# 9046.net
KiCad netlist of a schematic drawn in Altium Designer
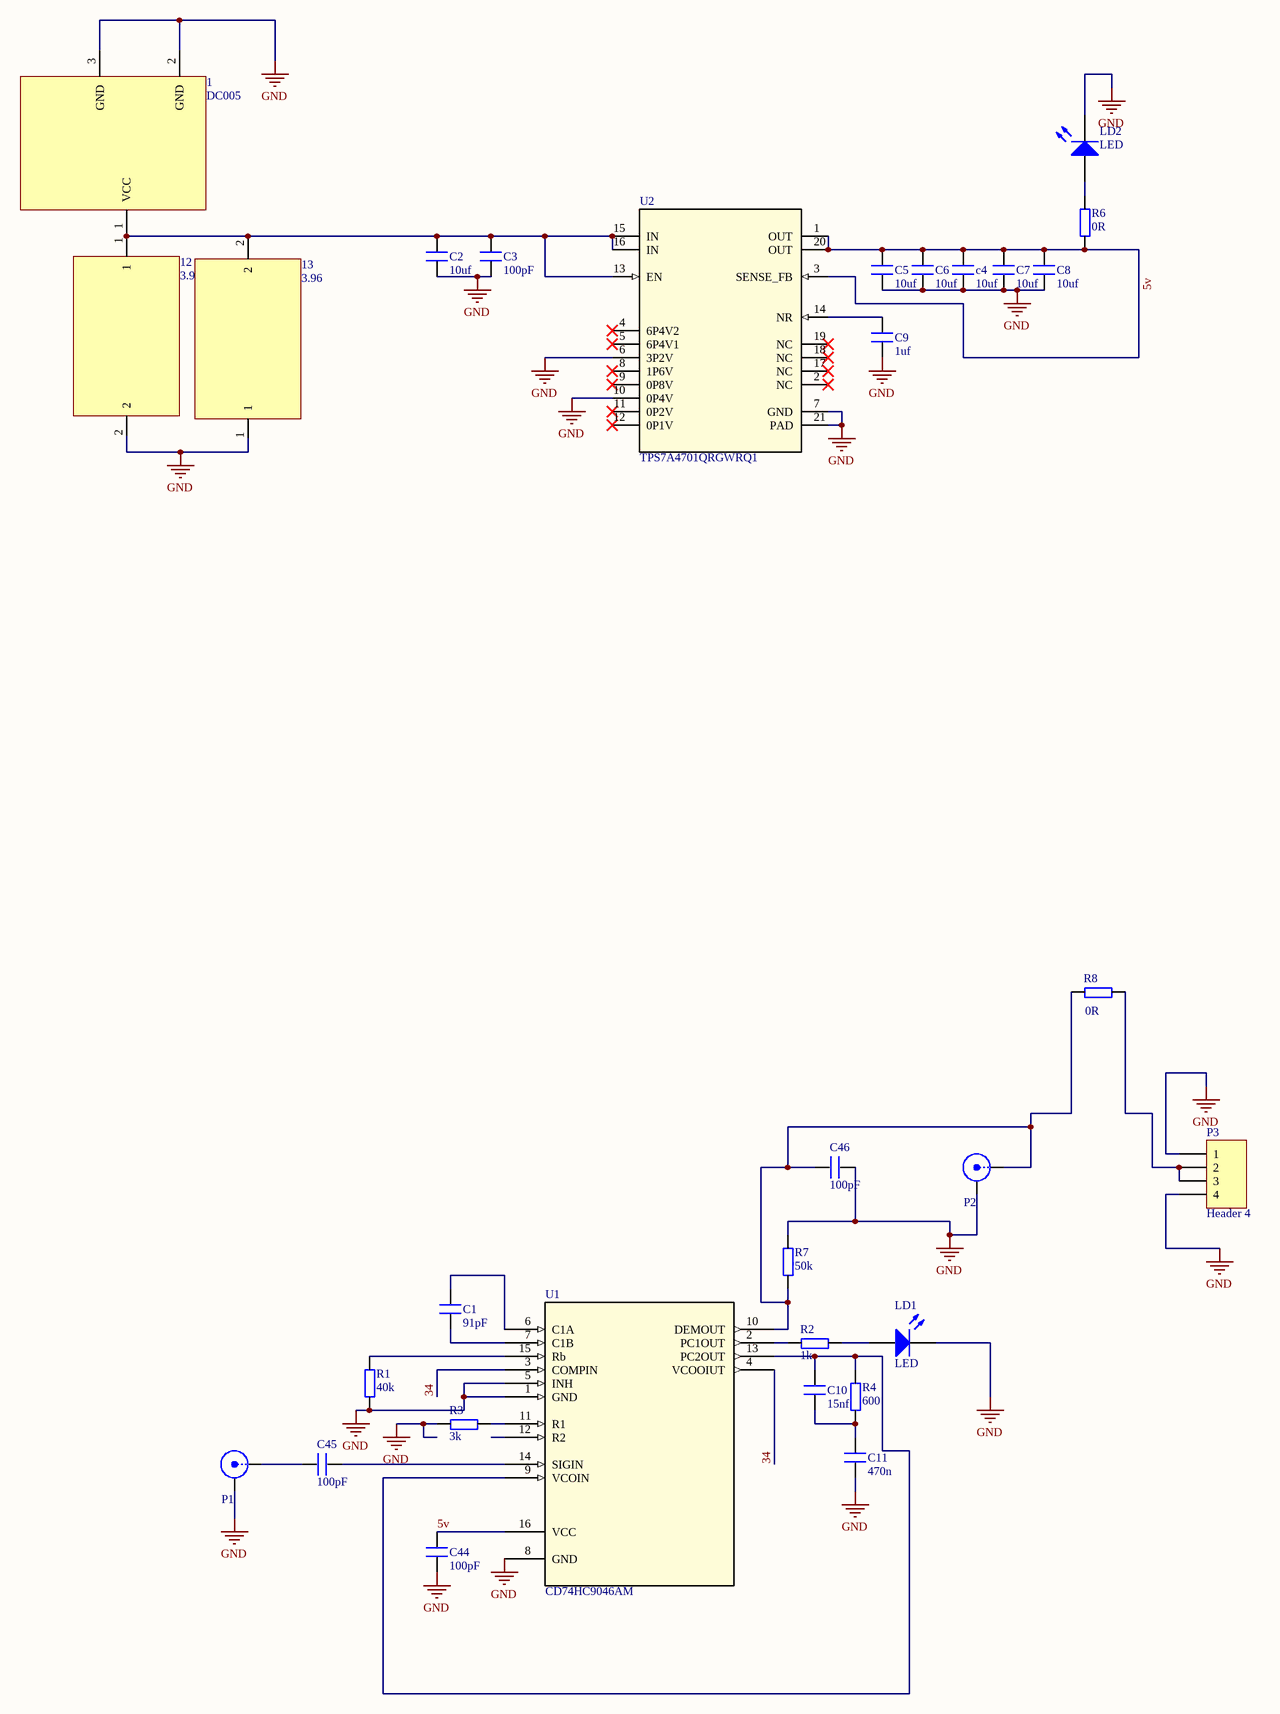
[diagram p0: 9046.SchDoc]

(export (version "E")
  (design (tool "Eeschema 10.0.6"))
  (components
    (comp (ref "1") (value "DC005") (footprint "DC10B") (libsource (lib "MYLIB") (part "DC005")))
    (comp (ref "12") (value "3.96") (footprint "3.96") (libsource (lib "MYLIB") (part "3.96")))
    (comp (ref "13") (value "3.96") (footprint "3.96") (libsource (lib "") (part "3.96_1")))
    (comp (ref "C1")
      (value "91pF")
      (footprint "0603C")
      (description "Capacitor")
      (libsource (lib "MYLIB") (part "C"))
    )
    (comp (ref "C2")
      (value "10uf")
      (footprint "0603C")
      (description "Capacitor")
      (libsource (lib "MYLIB") (part "C"))
    )
    (comp (ref "C3")
      (value "100pF")
      (footprint "0603C")
      (description "Capacitor")
      (libsource (lib "MYLIB") (part "C"))
    )
    (comp (ref "c4")
      (value "10uf")
      (footprint "0603C")
      (description "Capacitor")
      (libsource (lib "MYLIB") (part "C"))
    )
    (comp (ref "C5")
      (value "10uf")
      (footprint "0603C")
      (description "Capacitor")
      (libsource (lib "MYLIB") (part "C"))
    )
    (comp (ref "C6")
      (value "10uf")
      (footprint "0603C")
      (description "Capacitor")
      (libsource (lib "MYLIB") (part "C"))
    )
    (comp (ref "C7")
      (value "10uf")
      (footprint "0603C")
      (description "Capacitor")
      (libsource (lib "MYLIB") (part "C"))
    )
    (comp (ref "C8")
      (value "10uf")
      (footprint "0603C")
      (description "Capacitor")
      (libsource (lib "MYLIB") (part "C"))
    )
    (comp (ref "C9")
      (value "1uf")
      (footprint "0603C")
      (description "Capacitor")
      (libsource (lib "MYLIB") (part "C"))
    )
    (comp (ref "C10")
      (value "15nf")
      (footprint "0603C")
      (description "Capacitor")
      (libsource (lib "MYLIB") (part "C"))
    )
    (comp (ref "C11")
      (value "470n")
      (footprint "0603C")
      (description "Capacitor")
      (libsource (lib "MYLIB") (part "C"))
    )
    (comp (ref "C44")
      (value "100pF")
      (footprint "0603C")
      (description "Capacitor")
      (libsource (lib "MYLIB") (part "C"))
    )
    (comp (ref "C45")
      (value "100pF")
      (footprint "0603C")
      (description "Capacitor")
      (libsource (lib "MYLIB") (part "C"))
    )
    (comp (ref "C46")
      (value "100pF")
      (footprint "0603C")
      (description "Capacitor")
      (libsource (lib "MYLIB") (part "C"))
    )
    (comp (ref "LD1")
      (value "LED")
      (footprint "SMDLED")
      (description "Typical RED, GREEN, YELLOW, AMBER GaAs LED")
      (fields (field (name "PUBLISHER") "Altium Limited"))
      (libsource (lib "MYLIB") (part "LED"))
    )
    (comp (ref "LD2")
      (value "LED")
      (footprint "SMDLED")
      (description "Typical RED, GREEN, YELLOW, AMBER GaAs LED")
      (fields (field (name "PUBLISHER") "Altium Limited"))
      (libsource (lib "MYLIB") (part "LED"))
    )
    (comp (ref "P1")
      (value "SMA")
      (footprint "SMA")
      (description "SMA Connector")
      (libsource (lib "MYLIB") (part "SMA"))
    )
    (comp (ref "P2")
      (value "SMA")
      (footprint "SMA")
      (description "SMA Connector")
      (libsource (lib "MYLIB") (part "SMA"))
    )
    (comp (ref "P3")
      (value "Header 4")
      (footprint "HDR1X4")
      (description "Header, 4-Pin")
      (fields (field (name "PUBLISHER") "Altium Limited"))
      (libsource (lib "MYLIB") (part "Header 4"))
    )
    (comp (ref "R1")
      (value "40k")
      (footprint "0603R")
      (description "Resistor")
      (libsource (lib "MYLIB") (part "Resistor"))
    )
    (comp (ref "R2")
      (value "1k")
      (footprint "0603R")
      (description "Resistor")
      (libsource (lib "MYLIB") (part "Resistor"))
    )
    (comp (ref "R3")
      (value "3k")
      (footprint "0603R")
      (description "Resistor")
      (libsource (lib "MYLIB") (part "Resistor"))
    )
    (comp (ref "R4")
      (value "600")
      (footprint "0603R")
      (description "Resistor")
      (libsource (lib "MYLIB") (part "Resistor"))
    )
    (comp (ref "R6")
      (value "0R")
      (footprint "0603R")
      (description "Resistor")
      (libsource (lib "MYLIB") (part "Resistor"))
    )
    (comp (ref "R7")
      (value "50k")
      (footprint "0603R")
      (description "Resistor")
      (libsource (lib "MYLIB") (part "Resistor"))
    )
    (comp (ref "R8")
      (value "0R")
      (footprint "0603R")
      (description "Resistor")
      (libsource (lib "MYLIB") (part "Resistor"))
    )
    (comp (ref "U1")
      (value "CD74HC9046AM")
      (footprint "D16")
      (description "High Speed CMOS Logic Phase-Locked Loop with VCO and Lock Detector")
      (fields
        (field (name "MANUFACTURER") "Texas Instruments")
        (field (name "GENERIC_PART_NUMBER") "CD74HC7046A")
        (field (name "COPYRIGHT") "Copyright (C) 2018 Accelerated Designs. All rights reserved")
      )
      (libsource (lib "MYLIB") (part "CD74HC9046AM"))
    )
    (comp (ref "U2")
      (value "TPS7A4701QRGWRQ1")
      (footprint "RGW0020A")
      (description "No Description Available")
      (fields
        (field (name "MANUFACTURER") "Texas Instruments")
        (field (name "COPYRIGHT") "Copyright (C) 2018 Accelerated Designs. All rights reserved")
      )
      (libsource (lib "MYLIB") (part "TPS7A4701QRGWRQ1"))
    )
  )
  (nets
    (net (code "1") (name "/5v") (class "Default")
      (node (ref "C44") (pin "2") (pintype "passive"))
      (node (ref "C5") (pin "2") (pintype "passive"))
      (node (ref "C6") (pin "2") (pintype "passive"))
      (node (ref "C7") (pin "2") (pintype "passive"))
      (node (ref "C8") (pin "2") (pintype "passive"))
      (node (ref "R6") (pin "1") (pintype "passive"))
      (node (ref "U1") (pin "16") (pinfunction "VCC_16") (pintype "power_in"))
      (node (ref "U2") (pin "1") (pinfunction "OUT_1") (pintype "power_in"))
      (node (ref "U2") (pin "20") (pinfunction "OUT_20") (pintype "power_in"))
      (node (ref "U2") (pin "3") (pinfunction "SENSE_FB_3") (pintype "input"))
      (node (ref "c4") (pin "2") (pintype "passive"))
    )
    (net (code "2") (name "/34") (class "Default")
      (node (ref "U1") (pin "3") (pinfunction "COMPIN_3") (pintype "input"))
      (node (ref "U1") (pin "4") (pinfunction "VCOOIUT_4") (pintype "output"))
    )
    (net (code "3") (name "GND") (class "Default")
      (node (ref "1") (pin "2") (pinfunction "GND_2") (pintype "passive"))
      (node (ref "1") (pin "3") (pinfunction "GND_3") (pintype "passive"))
      (node (ref "12") (pin "2") (pinfunction "2_2") (pintype "passive"))
      (node (ref "13") (pin "1") (pinfunction "1_1") (pintype "passive"))
      (node (ref "C11") (pin "2") (pintype "passive"))
      (node (ref "C2") (pin "1") (pintype "passive"))
      (node (ref "C3") (pin "1") (pintype "passive"))
      (node (ref "C44") (pin "1") (pintype "passive"))
      (node (ref "C46") (pin "2") (pintype "passive"))
      (node (ref "C5") (pin "1") (pintype "passive"))
      (node (ref "C6") (pin "1") (pintype "passive"))
      (node (ref "C7") (pin "1") (pintype "passive"))
      (node (ref "C8") (pin "1") (pintype "passive"))
      (node (ref "C9") (pin "1") (pintype "passive"))
      (node (ref "LD1") (pin "2") (pinfunction "K_2") (pintype "passive"))
      (node (ref "LD2") (pin "2") (pinfunction "K_2") (pintype "passive"))
      (node (ref "P1") (pin "2") (pinfunction "Y_2") (pintype "passive"))
      (node (ref "P2") (pin "2") (pinfunction "Y_2") (pintype "passive"))
      (node (ref "P3") (pin "1") (pinfunction "1_1") (pintype "passive"))
      (node (ref "P3") (pin "4") (pinfunction "4_4") (pintype "passive"))
      (node (ref "R1") (pin "1") (pintype "passive"))
      (node (ref "R3") (pin "1") (pintype "passive"))
      (node (ref "R7") (pin "2") (pintype "passive"))
      (node (ref "U1") (pin "1") (pinfunction "GND_1") (pintype "input"))
      (node (ref "U1") (pin "5") (pinfunction "INH_5") (pintype "input"))
      (node (ref "U1") (pin "8") (pinfunction "GND_8") (pintype "power_in"))
      (node (ref "U2") (pin "10") (pinfunction "0P4V_10") (pintype "passive"))
      (node (ref "U2") (pin "21") (pinfunction "PAD_21") (pintype "passive"))
      (node (ref "U2") (pin "6") (pinfunction "3P2V_6") (pintype "passive"))
      (node (ref "U2") (pin "7") (pinfunction "GND_7") (pintype "power_in"))
      (node (ref "c4") (pin "1") (pintype "passive"))
    )
    (net (code "4") (name "Net-(1-VCC)") (class "Default")
      (node (ref "1") (pin "1") (pinfunction "VCC_1") (pintype "passive"))
      (node (ref "12") (pin "1") (pinfunction "1_1") (pintype "passive"))
      (node (ref "13") (pin "2") (pinfunction "2_2") (pintype "passive"))
      (node (ref "C2") (pin "2") (pintype "passive"))
      (node (ref "C3") (pin "2") (pintype "passive"))
      (node (ref "U2") (pin "13") (pinfunction "EN_13") (pintype "input"))
      (node (ref "U2") (pin "15") (pinfunction "IN_15") (pintype "power_in"))
      (node (ref "U2") (pin "16") (pinfunction "IN_16") (pintype "power_in"))
    )
    (net (code "5") (name "Net-(C10-Pad2)") (class "Default")
      (node (ref "C10") (pin "2") (pintype "passive"))
      (node (ref "C11") (pin "1") (pintype "passive"))
      (node (ref "R4") (pin "1") (pintype "passive"))
    )
    (net (code "6") (name "Net-(LD1-A)") (class "Default")
      (node (ref "LD1") (pin "1") (pinfunction "A_1") (pintype "passive"))
      (node (ref "R2") (pin "2") (pintype "passive"))
    )
    (net (code "7") (name "Net-(LD2-A)") (class "Default")
      (node (ref "LD2") (pin "1") (pinfunction "A_1") (pintype "passive"))
      (node (ref "R6") (pin "2") (pintype "passive"))
    )
    (net (code "8") (name "Net-(P1-X)") (class "Default")
      (node (ref "C45") (pin "1") (pintype "passive"))
      (node (ref "P1") (pin "1") (pinfunction "X_1") (pintype "passive"))
    )
    (net (code "9") (name "Net-(P2-X)") (class "Default")
      (node (ref "C46") (pin "1") (pintype "passive"))
      (node (ref "P2") (pin "1") (pinfunction "X_1") (pintype "passive"))
      (node (ref "R7") (pin "1") (pintype "passive"))
      (node (ref "R8") (pin "1") (pintype "passive"))
      (node (ref "U1") (pin "10") (pinfunction "DEMOUT_10") (pintype "output"))
    )
    (net (code "10") (name "Net-(P3-Pad2)") (class "Default")
      (node (ref "P3") (pin "2") (pinfunction "2_2") (pintype "passive"))
      (node (ref "P3") (pin "3") (pinfunction "3_3") (pintype "passive"))
      (node (ref "R8") (pin "2") (pintype "passive"))
    )
    (net (code "11") (name "Net-(U1-C1A)") (class "Default")
      (node (ref "C1") (pin "2") (pintype "passive"))
      (node (ref "U1") (pin "6") (pinfunction "C1A_6") (pintype "input"))
    )
    (net (code "12") (name "Net-(U1-C1B)") (class "Default")
      (node (ref "C1") (pin "1") (pintype "passive"))
      (node (ref "U1") (pin "7") (pinfunction "C1B_7") (pintype "input"))
    )
    (net (code "13") (name "Net-(U1-PC1OUT)") (class "Default")
      (node (ref "R2") (pin "1") (pintype "passive"))
      (node (ref "U1") (pin "2") (pinfunction "PC1OUT_2") (pintype "output"))
    )
    (net (code "14") (name "Net-(U1-PC2OUT)") (class "Default")
      (node (ref "C10") (pin "1") (pintype "passive"))
      (node (ref "R4") (pin "2") (pintype "passive"))
      (node (ref "U1") (pin "13") (pinfunction "PC2OUT_13") (pintype "output"))
      (node (ref "U1") (pin "9") (pinfunction "VCOIN_9") (pintype "input"))
    )
    (net (code "15") (name "Net-(U1-R1)") (class "Default")
      (node (ref "R3") (pin "2") (pintype "passive"))
      (node (ref "U1") (pin "11") (pinfunction "R1_11") (pintype "input"))
    )
    (net (code "16") (name "Net-(U1-Rb)") (class "Default")
      (node (ref "R1") (pin "2") (pintype "passive"))
      (node (ref "U1") (pin "15") (pinfunction "Rb_15") (pintype "input"))
    )
    (net (code "17") (name "Net-(U1-SIGIN)") (class "Default")
      (node (ref "C45") (pin "2") (pintype "passive"))
      (node (ref "U1") (pin "14") (pinfunction "SIGIN_14") (pintype "input"))
    )
    (net (code "18") (name "Net-(U2-NR)") (class "Default")
      (node (ref "C9") (pin "2") (pintype "passive"))
      (node (ref "U2") (pin "14") (pinfunction "NR_14") (pintype "input"))
    )
    (net (code "19") (name "unconnected-(U1-R2-Pad12)") (class "Default")
      (node (ref "U1") (pin "12") (pinfunction "R2_12") (pintype "input"))
    )
    (net (code "20") (name "unconnected-(U2-0P1V-Pad12)") (class "Default")
      (node (ref "U2") (pin "12") (pinfunction "0P1V_12") (pintype "passive+no_connect"))
    )
    (net (code "21") (name "unconnected-(U2-0P2V-Pad11)") (class "Default")
      (node (ref "U2") (pin "11") (pinfunction "0P2V_11") (pintype "passive+no_connect"))
    )
    (net (code "22") (name "unconnected-(U2-0P8V-Pad9)") (class "Default")
      (node (ref "U2") (pin "9") (pinfunction "0P8V_9") (pintype "passive+no_connect"))
    )
    (net (code "23") (name "unconnected-(U2-1P6V-Pad8)") (class "Default")
      (node (ref "U2") (pin "8") (pinfunction "1P6V_8") (pintype "passive+no_connect"))
    )
    (net (code "24") (name "unconnected-(U2-6P4V1-Pad5)") (class "Default")
      (node (ref "U2") (pin "5") (pinfunction "6P4V1_5") (pintype "passive+no_connect"))
    )
    (net (code "25") (name "unconnected-(U2-6P4V2-Pad4)") (class "Default")
      (node (ref "U2") (pin "4") (pinfunction "6P4V2_4") (pintype "passive+no_connect"))
    )
    (net (code "26") (name "unconnected-(U2-NC-Pad2)") (class "Default")
      (node (ref "U2") (pin "2") (pinfunction "NC_2") (pintype "passive+no_connect"))
    )
    (net (code "27") (name "unconnected-(U2-NC-Pad17)") (class "Default")
      (node (ref "U2") (pin "17") (pinfunction "NC_17") (pintype "passive+no_connect"))
    )
    (net (code "28") (name "unconnected-(U2-NC-Pad18)") (class "Default")
      (node (ref "U2") (pin "18") (pinfunction "NC_18") (pintype "passive+no_connect"))
    )
    (net (code "29") (name "unconnected-(U2-NC-Pad19)") (class "Default")
      (node (ref "U2") (pin "19") (pinfunction "NC_19") (pintype "passive+no_connect"))
    )
  )
)
